# SwitchingPowerSupplyCourse.net
KiCad netlist of a schematic drawn in Altium Designer
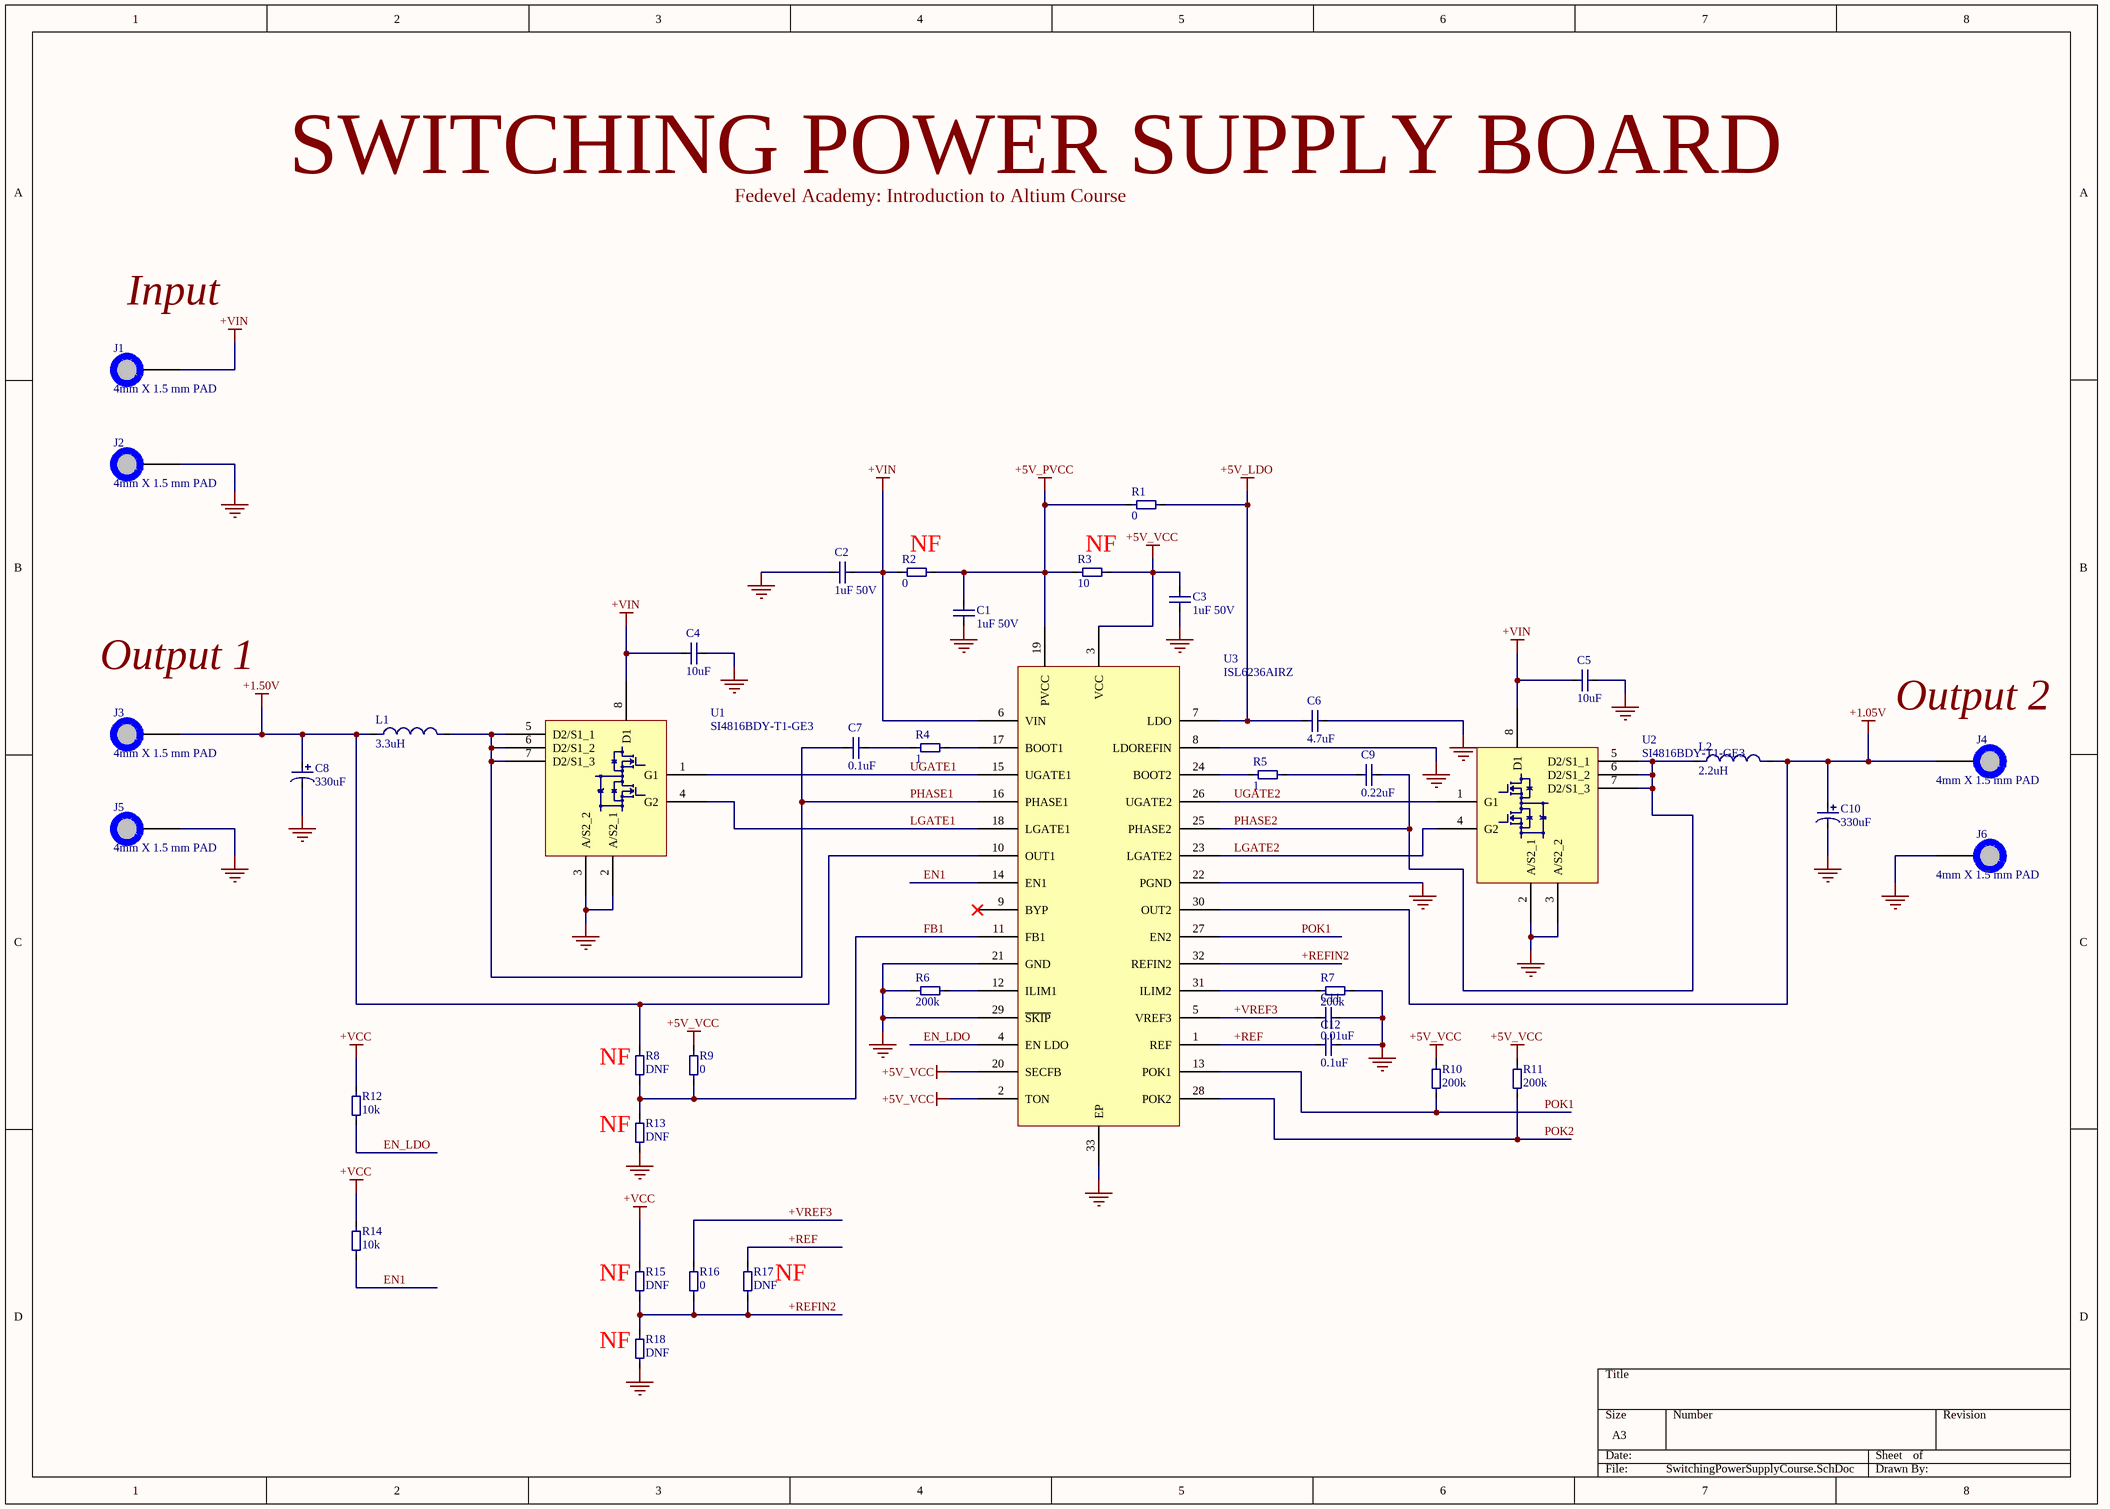
[diagram p0: SwitchingPowerSupplyCourse.SchDoc]

(export (version "E")
  (design (tool "Eeschema 10.0.6"))
  (components
    (comp (ref "C1")
      (value "1uF 50V")
      (footprint "C0805")
      (description "Multilayer Ceramic Capacitors MLCC - SMD/SMT CAP MLCC 0805 50V Y5V 1uF +80/-20%")
      (fields
        (field (name "MANUFACTURER") "Taiyo Yuden")
        (field (name "MANUFACTURER PART NUMBER") "UMK212F105ZG-T")
      )
      (libsource (lib "SwitchingPowerSupplyCourse_Symbols") (part "UMK212F105ZG-T"))
    )
    (comp (ref "C2")
      (value "1uF 50V")
      (footprint "C0805")
      (description "Multilayer Ceramic Capacitors MLCC - SMD/SMT CAP MLCC 0805 50V Y5V 1uF +80/-20%")
      (fields
        (field (name "MANUFACTURER") "Taiyo Yuden")
        (field (name "MANUFACTURER PART NUMBER") "UMK212F105ZG-T")
      )
      (libsource (lib "SwitchingPowerSupplyCourse_Symbols") (part "UMK212F105ZG-T"))
    )
    (comp (ref "C3")
      (value "1uF 50V")
      (footprint "C0805")
      (description "Multilayer Ceramic Capacitors MLCC - SMD/SMT CAP MLCC 0805 50V Y5V 1uF +80/-20%")
      (fields
        (field (name "MANUFACTURER") "Taiyo Yuden")
        (field (name "MANUFACTURER PART NUMBER") "UMK212F105ZG-T")
      )
      (libsource (lib "SwitchingPowerSupplyCourse_Symbols") (part "UMK212F105ZG-T"))
    )
    (comp (ref "C4")
      (value "10uF")
      (footprint "C1210")
      (description "Multilayer Ceramic Capacitors MLCC - SMD/SMT CAP MLCC 1210 50V X5R 10uF 20%")
      (fields
        (field (name "MANUFACTURER") "Taiyo Yuden")
        (field (name "MANUFACTURER PART NUMBER") "UMK325BJ106MM-T")
      )
      (libsource (lib "SwitchingPowerSupplyCourse_Symbols") (part "UMK325BJ106MM-T"))
    )
    (comp (ref "C5")
      (value "10uF")
      (footprint "C1210")
      (description "Multilayer Ceramic Capacitors MLCC - SMD/SMT CAP MLCC 1210 50V X5R 10uF 20%")
      (fields
        (field (name "MANUFACTURER") "Taiyo Yuden")
        (field (name "MANUFACTURER PART NUMBER") "UMK325BJ106MM-T")
      )
      (libsource (lib "SwitchingPowerSupplyCourse_Symbols") (part "UMK325BJ106MM-T"))
    )
    (comp (ref "C6")
      (value "4.7uF")
      (footprint "C1206")
      (description "Multilayer Ceramic Capacitors MLCC - SMD/SMT 1206 4.7uF 10volts X5R 10%")
      (fields (field (name "MANUFACTURER") "AVX") (field (name "MANUFACTURER PART NUMBER") "1206ZD475KAT2A"))
      (libsource (lib "SwitchingPowerSupplyCourse_Symbols") (part "1206ZD475KAT2A"))
    )
    (comp (ref "C7")
      (value "0.1uF")
      (footprint "C0805")
      (description "Multilayer Ceramic Capacitors MLCC - SMD/SMT 50volts 0.1uF 10%")
      (fields
        (field (name "MANUFACTURER") "Syfer")
        (field (name "MANUFACTURER PART NUMBER") "0805J0500104KJT")
      )
      (libsource (lib "SwitchingPowerSupplyCourse_Symbols") (part "0805J0500104KJT"))
    )
    (comp (ref "C8")
      (value "330uF")
      (footprint "7343-31")
      (description "Tantalum Capacitors - Solid SMD 10volts 330uF 10% ESR=150mOhms")
      (fields
        (field (name "MANUFACTURER") "Kemet")
        (field (name "MANUFACTURER PART NUMBER") "T495D337K010ATE150")
      )
      (libsource (lib "SwitchingPowerSupplyCourse_Symbols") (part "T495D337K010ATE150"))
    )
    (comp (ref "C9")
      (value "0.22uF")
      (footprint "C0805")
      (description "Multilayer Ceramic Capacitors MLCC - SMD/SMT CAP MLCC 0805 50V X7R 0.22uF 10%")
      (fields
        (field (name "MANUFACTURER") "Taiyo Yuden")
        (field (name "MANUFACTURER PART NUMBER") "UMK212B7224KG-T")
      )
      (libsource (lib "SwitchingPowerSupplyCourse_Symbols") (part "UMK212B7224KG-T"))
    )
    (comp (ref "C10")
      (value "330uF")
      (footprint "7343-31")
      (description "Tantalum Capacitors - Solid SMD 10volts 330uF 10% ESR=150mOhms")
      (fields
        (field (name "MANUFACTURER") "Kemet")
        (field (name "MANUFACTURER PART NUMBER") "T495D337K010ATE150")
      )
      (libsource (lib "SwitchingPowerSupplyCourse_Symbols") (part "T495D337K010ATE150"))
    )
    (comp (ref "C11")
      (value "0.01uF")
      (footprint "C0805")
      (description "Multilayer Ceramic Capacitors MLCC - SMD/SMT 0805 0.01uF 50volts X7R 5%")
      (fields
        (field (name "MANUFACTURER") "Vishay / Vitramon")
        (field (name "MANUFACTURER PART NUMBER") "VJ0805Y103JXAPW1BC")
      )
      (libsource (lib "SwitchingPowerSupplyCourse_Symbols") (part "VJ0805Y103JXAPW1BC"))
    )
    (comp (ref "C12")
      (value "0.1uF")
      (footprint "C0805")
      (description "Multilayer Ceramic Capacitors MLCC - SMD/SMT 50volts 0.1uF 10%")
      (fields
        (field (name "MANUFACTURER") "Syfer")
        (field (name "MANUFACTURER PART NUMBER") "0805J0500104KJT")
      )
      (libsource (lib "SwitchingPowerSupplyCourse_Symbols") (part "0805J0500104KJT"))
    )
    (comp (ref "J1")
      (value "4mm X 1.5 mm PAD")
      (footprint "PAD_WITH_HOLE_4mmX1.5mm")
      (description "Elliptical pad 4mm x 1.5 mm")
      (libsource (lib "SwitchingPowerSupplyCourse_Symbols") (part "4mmX1.5mm_PAD"))
    )
    (comp (ref "J2")
      (value "4mm X 1.5 mm PAD")
      (footprint "PAD_WITH_HOLE_4mmX1.5mm")
      (description "Elliptical pad 4mm x 1.5 mm")
      (libsource (lib "SwitchingPowerSupplyCourse_Symbols") (part "4mmX1.5mm_PAD"))
    )
    (comp (ref "J3")
      (value "4mm X 1.5 mm PAD")
      (footprint "PAD_WITH_HOLE_4mmX1.5mm")
      (description "Elliptical pad 4mm x 1.5 mm")
      (libsource (lib "SwitchingPowerSupplyCourse_Symbols") (part "4mmX1.5mm_PAD"))
    )
    (comp (ref "J4")
      (value "4mm X 1.5 mm PAD")
      (footprint "PAD_WITH_HOLE_4mmX1.5mm")
      (description "Elliptical pad 4mm x 1.5 mm")
      (libsource (lib "SwitchingPowerSupplyCourse_Symbols") (part "4mmX1.5mm_PAD"))
    )
    (comp (ref "J5")
      (value "4mm X 1.5 mm PAD")
      (footprint "PAD_WITH_HOLE_4mmX1.5mm")
      (description "Elliptical pad 4mm x 1.5 mm")
      (libsource (lib "SwitchingPowerSupplyCourse_Symbols") (part "4mmX1.5mm_PAD"))
    )
    (comp (ref "J6")
      (value "4mm X 1.5 mm PAD")
      (footprint "PAD_WITH_HOLE_4mmX1.5mm")
      (description "Elliptical pad 4mm x 1.5 mm")
      (libsource (lib "SwitchingPowerSupplyCourse_Symbols") (part "4mmX1.5mm_PAD"))
    )
    (comp (ref "L1")
      (value "3.3uH")
      (footprint "SRP1265A")
      (description "Fixed Inductors 3.3uH 20% SMD 1265")
      (fields
        (field (name "MANUFACTURER") "Bourns")
        (field (name "MANUFACTURER PART NUMBER") "SRP1265A-3R3M")
      )
      (libsource (lib "SwitchingPowerSupplyCourse_Symbols") (part "SRP1265A-3R3M"))
    )
    (comp (ref "L2")
      (value "2.2uH")
      (footprint "SRP1265A")
      (description "Fixed Inductors 2.2uH 20% SMD 1265")
      (fields
        (field (name "MANUFACTURER") "Bourns")
        (field (name "MANUFACTURER PART NUMBER") "SRP1265A-2R2M")
      )
      (libsource (lib "SwitchingPowerSupplyCourse_Symbols") (part "SRP1265A-2R2M"))
    )
    (comp (ref "R1")
      (value "0")
      (footprint "R0805")
      (description "Thick Film Resistors - SMD ZEROohms JUMPER")
      (fields
        (field (name "MANUFACTURER") "KOA Speer")
        (field (name "MANUFACTURER PART NUMBER") "RK73Z2ATTD")
      )
      (libsource (lib "SwitchingPowerSupplyCourse_Symbols") (part "RK73Z2ATTD"))
    )
    (comp (ref "R2")
      (value "0")
      (footprint "R0805")
      (description "Thick Film Resistors - SMD ZEROohms JUMPER")
      (fields
        (field (name "MANUFACTURER") "KOA Speer")
        (field (name "MANUFACTURER PART NUMBER") "RK73Z2ATTD")
      )
      (libsource (lib "SwitchingPowerSupplyCourse_Symbols") (part "RK73Z2ATTD"))
    )
    (comp (ref "R3")
      (value "10")
      (footprint "R0805")
      (description "Thick Film Resistors - SMD 1/8watt 10ohms 1% 100ppm")
      (fields
        (field (name "MANUFACTURER") "Vishay / Dale")
        (field (name "MANUFACTURER PART NUMBER") "CRCW080510R0FKEA")
      )
      (libsource (lib "SwitchingPowerSupplyCourse_Symbols") (part "CRCW080510R0FKEA"))
    )
    (comp (ref "R4")
      (value "1")
      (footprint "R0805")
      (description "Thick Film Resistors - SMD 1/8watt 1ohms 100ppm")
      (fields
        (field (name "MANUFACTURER") "Vishay / Dale")
        (field (name "MANUFACTURER PART NUMBER") "CRCW08051R00FKEA")
      )
      (libsource (lib "SwitchingPowerSupplyCourse_Symbols") (part "CRCW08051R00FKEA"))
    )
    (comp (ref "R5")
      (value "1")
      (footprint "R0805")
      (description "Thick Film Resistors - SMD 1/8watt 1ohms 100ppm")
      (fields
        (field (name "MANUFACTURER") "Vishay / Dale")
        (field (name "MANUFACTURER PART NUMBER") "CRCW08051R00FKEA")
      )
      (libsource (lib "SwitchingPowerSupplyCourse_Symbols") (part "CRCW08051R00FKEA"))
    )
    (comp (ref "R6")
      (value "200k")
      (footprint "R0805")
      (description "Thick Film Resistors - SMD 1/8watts 200Kohms 1%")
      (fields
        (field (name "MANUFACTURER") "KOA Speer")
        (field (name "MANUFACTURER PART NUMBER") "RK73H2ATTD2003F")
      )
      (libsource (lib "SwitchingPowerSupplyCourse_Symbols") (part "RK73H2ATTD2003F"))
    )
    (comp (ref "R7")
      (value "200k")
      (footprint "R0805")
      (description "Thick Film Resistors - SMD 1/8watts 200Kohms 1%")
      (fields
        (field (name "MANUFACTURER") "KOA Speer")
        (field (name "MANUFACTURER PART NUMBER") "RK73H2ATTD2003F")
      )
      (libsource (lib "SwitchingPowerSupplyCourse_Symbols") (part "RK73H2ATTD2003F"))
    )
    (comp (ref "R8")
      (value "DNF")
      (footprint "R0805")
      (description "Generic Do Not Fit Capacitor")
      (libsource (lib "SwitchingPowerSupplyCourse_Symbols") (part "RES"))
    )
    (comp (ref "R9")
      (value "0")
      (footprint "R0805")
      (description "Thick Film Resistors - SMD ZEROohms JUMPER")
      (fields
        (field (name "MANUFACTURER") "KOA Speer")
        (field (name "MANUFACTURER PART NUMBER") "RK73Z2ATTD")
      )
      (libsource (lib "SwitchingPowerSupplyCourse_Symbols") (part "RK73Z2ATTD"))
    )
    (comp (ref "R10")
      (value "200k")
      (footprint "R0805")
      (description "Thick Film Resistors - SMD 1/8watts 200Kohms 1%")
      (fields
        (field (name "MANUFACTURER") "KOA Speer")
        (field (name "MANUFACTURER PART NUMBER") "RK73H2ATTD2003F")
      )
      (libsource (lib "SwitchingPowerSupplyCourse_Symbols") (part "RK73H2ATTD2003F"))
    )
    (comp (ref "R11")
      (value "200k")
      (footprint "R0805")
      (description "Thick Film Resistors - SMD 1/8watts 200Kohms 1%")
      (fields
        (field (name "MANUFACTURER") "KOA Speer")
        (field (name "MANUFACTURER PART NUMBER") "RK73H2ATTD2003F")
      )
      (libsource (lib "SwitchingPowerSupplyCourse_Symbols") (part "RK73H2ATTD2003F"))
    )
    (comp (ref "R12")
      (value "10k")
      (footprint "R0805")
      (description "Thick Film Resistors - SMD 0.25W 10Kohm 1% 200ppm")
      (fields
        (field (name "MANUFACTURER") "KOA Speer")
        (field (name "MANUFACTURER PART NUMBER") "SG73P2ATTD1002F")
      )
      (libsource (lib "SwitchingPowerSupplyCourse_Symbols") (part "SG73P2ATTD1002F"))
    )
    (comp (ref "R13")
      (value "DNF")
      (footprint "R0805")
      (description "Generic Do Not Fit Capacitor")
      (libsource (lib "SwitchingPowerSupplyCourse_Symbols") (part "RES"))
    )
    (comp (ref "R14")
      (value "10k")
      (footprint "R0805")
      (description "Thick Film Resistors - SMD 0.25W 10Kohm 1% 200ppm")
      (fields
        (field (name "MANUFACTURER") "KOA Speer")
        (field (name "MANUFACTURER PART NUMBER") "SG73P2ATTD1002F")
      )
      (libsource (lib "SwitchingPowerSupplyCourse_Symbols") (part "SG73P2ATTD1002F"))
    )
    (comp (ref "R15")
      (value "DNF")
      (footprint "R0805")
      (description "Generic Do Not Fit Capacitor")
      (libsource (lib "SwitchingPowerSupplyCourse_Symbols") (part "RES"))
    )
    (comp (ref "R16")
      (value "0")
      (footprint "R0805")
      (description "Thick Film Resistors - SMD ZEROohms JUMPER")
      (fields
        (field (name "MANUFACTURER") "KOA Speer")
        (field (name "MANUFACTURER PART NUMBER") "RK73Z2ATTD")
      )
      (libsource (lib "SwitchingPowerSupplyCourse_Symbols") (part "RK73Z2ATTD"))
    )
    (comp (ref "R17")
      (value "DNF")
      (footprint "R0805")
      (description "Generic Do Not Fit Capacitor")
      (libsource (lib "SwitchingPowerSupplyCourse_Symbols") (part "RES"))
    )
    (comp (ref "R18")
      (value "DNF")
      (footprint "R0805")
      (description "Generic Do Not Fit Capacitor")
      (libsource (lib "SwitchingPowerSupplyCourse_Symbols") (part "RES"))
    )
    (comp (ref "U1")
      (value "SI4816BDY-T1-GE3")
      (footprint "SO-8")
      (description "MOSFET Dua lN-Ch w/Schottky 30V 18.5/11.5mohm")
      (fields (field (name "MANUFACTURER") "Vishay / Siliconix"))
      (libsource (lib "SwitchingPowerSupplyCourse_Symbols") (part "SI4816BDY-T1-GE3"))
    )
    (comp (ref "U2")
      (value "SI4816BDY-T1-GE3")
      (footprint "SO-8")
      (description "MOSFET Dua lN-Ch w/Schottky 30V 18.5/11.5mohm")
      (fields (field (name "MANUFACTURER") "Vishay / Siliconix"))
      (libsource (lib "SwitchingPowerSupplyCourse_Symbols") (part "SI4816BDY-T1-GE3"))
    )
    (comp (ref "U3")
      (value "ISL6236AIRZ")
      (footprint "L32.5x5B")
      (description "Switching Controllers ISL6236 QD QUTPUT CNTRLR IMVP-6 32LD")
      (fields (field (name "MANUFACTURER") "Intersil"))
      (libsource (lib "SwitchingPowerSupplyCourse_Symbols") (part "ISL6236AIRZ"))
    )
  )
  (nets
    (net (code "1") (name "+1.05V") (class "Default")
      (node (ref "C10") (pin "1") (pinfunction "1_1") (pintype "passive"))
      (node (ref "J4") (pin "1") (pinfunction "1_1") (pintype "passive"))
      (node (ref "L2") (pin "2") (pinfunction "2_2") (pintype "passive"))
      (node (ref "U3") (pin "30") (pinfunction "OUT2_30") (pintype "passive"))
    )
    (net (code "2") (name "+1.50V") (class "Default")
      (node (ref "C8") (pin "1") (pinfunction "1_1") (pintype "passive"))
      (node (ref "J3") (pin "1") (pinfunction "1_1") (pintype "passive"))
      (node (ref "L1") (pin "1") (pinfunction "1_1") (pintype "passive"))
      (node (ref "R8") (pin "2") (pinfunction "2_2") (pintype "passive"))
      (node (ref "U3") (pin "10") (pinfunction "OUT1_10") (pintype "passive"))
    )
    (net (code "3") (name "+5V_LDO") (class "Default")
      (node (ref "C6") (pin "2") (pinfunction "2_2") (pintype "passive"))
      (node (ref "R1") (pin "2") (pinfunction "2_2") (pintype "passive"))
      (node (ref "U3") (pin "7") (pinfunction "LDO_7") (pintype "passive"))
    )
    (net (code "4") (name "+5V_PVCC") (class "Default")
      (node (ref "C1") (pin "2") (pinfunction "2_2") (pintype "passive"))
      (node (ref "R1") (pin "1") (pinfunction "1_1") (pintype "passive"))
      (node (ref "R2") (pin "2") (pinfunction "2_2") (pintype "passive"))
      (node (ref "R3") (pin "1") (pinfunction "1_1") (pintype "passive"))
      (node (ref "U3") (pin "19") (pinfunction "PVCC_19") (pintype "passive"))
    )
    (net (code "5") (name "+5V_VCC") (class "Default")
      (node (ref "C3") (pin "1") (pinfunction "1_1") (pintype "passive"))
      (node (ref "R10") (pin "1") (pinfunction "1_1") (pintype "passive"))
      (node (ref "R11") (pin "1") (pinfunction "1_1") (pintype "passive"))
      (node (ref "R3") (pin "2") (pinfunction "2_2") (pintype "passive"))
      (node (ref "R9") (pin "2") (pinfunction "2_2") (pintype "passive"))
      (node (ref "U3") (pin "2") (pinfunction "TON_2") (pintype "passive"))
      (node (ref "U3") (pin "20") (pinfunction "SECFB_20") (pintype "passive"))
      (node (ref "U3") (pin "3") (pinfunction "VCC_3") (pintype "passive"))
    )
    (net (code "6") (name "+VCC") (class "Default")
      (node (ref "R12") (pin "2") (pinfunction "2_2") (pintype "passive"))
      (node (ref "R14") (pin "2") (pinfunction "2_2") (pintype "passive"))
      (node (ref "R15") (pin "2") (pinfunction "2_2") (pintype "passive"))
    )
    (net (code "7") (name "+VIN") (class "Default")
      (node (ref "C2") (pin "2") (pinfunction "2_2") (pintype "passive"))
      (node (ref "C4") (pin "1") (pinfunction "1_1") (pintype "passive"))
      (node (ref "C5") (pin "1") (pinfunction "1_1") (pintype "passive"))
      (node (ref "J1") (pin "1") (pinfunction "1_1") (pintype "passive"))
      (node (ref "R2") (pin "1") (pinfunction "1_1") (pintype "passive"))
      (node (ref "U1") (pin "8") (pinfunction "D1_8") (pintype "passive"))
      (node (ref "U2") (pin "8") (pinfunction "D1_8") (pintype "passive"))
      (node (ref "U3") (pin "6") (pinfunction "VIN_6") (pintype "passive"))
    )
    (net (code "8") (name "/+REF") (class "Default")
      (node (ref "C12") (pin "1") (pinfunction "1_1") (pintype "passive"))
      (node (ref "R17") (pin "2") (pinfunction "2_2") (pintype "passive"))
      (node (ref "U3") (pin "1") (pinfunction "REF_1") (pintype "passive"))
    )
    (net (code "9") (name "/+REFIN2") (class "Default")
      (node (ref "R15") (pin "1") (pinfunction "1_1") (pintype "passive"))
      (node (ref "R16") (pin "1") (pinfunction "1_1") (pintype "passive"))
      (node (ref "R17") (pin "1") (pinfunction "1_1") (pintype "passive"))
      (node (ref "R18") (pin "2") (pinfunction "2_2") (pintype "passive"))
      (node (ref "U3") (pin "32") (pinfunction "REFIN2_32") (pintype "passive"))
    )
    (net (code "10") (name "/+VREF3") (class "Default")
      (node (ref "C11") (pin "1") (pinfunction "1_1") (pintype "passive"))
      (node (ref "R16") (pin "2") (pinfunction "2_2") (pintype "passive"))
      (node (ref "U3") (pin "5") (pinfunction "VREF3_5") (pintype "passive"))
    )
    (net (code "11") (name "/EN1") (class "Default")
      (node (ref "R14") (pin "1") (pinfunction "1_1") (pintype "passive"))
      (node (ref "U3") (pin "14") (pinfunction "EN1_14") (pintype "passive"))
    )
    (net (code "12") (name "/EN_LDO") (class "Default")
      (node (ref "R12") (pin "1") (pinfunction "1_1") (pintype "passive"))
      (node (ref "U3") (pin "4") (pinfunction "EN_LDO_4") (pintype "passive"))
    )
    (net (code "13") (name "/FB1") (class "Default")
      (node (ref "R13") (pin "2") (pinfunction "2_2") (pintype "passive"))
      (node (ref "R8") (pin "1") (pinfunction "1_1") (pintype "passive"))
      (node (ref "R9") (pin "1") (pinfunction "1_1") (pintype "passive"))
      (node (ref "U3") (pin "11") (pinfunction "FB1_11") (pintype "passive"))
    )
    (net (code "14") (name "/LGATE1") (class "Default")
      (node (ref "U1") (pin "4") (pinfunction "G2_4") (pintype "passive"))
      (node (ref "U3") (pin "18") (pinfunction "LGATE1_18") (pintype "passive"))
    )
    (net (code "15") (name "/LGATE2") (class "Default")
      (node (ref "U2") (pin "4") (pinfunction "G2_4") (pintype "passive"))
      (node (ref "U3") (pin "23") (pinfunction "LGATE2_23") (pintype "passive"))
    )
    (net (code "16") (name "/PHASE1") (class "Default")
      (node (ref "C7") (pin "1") (pinfunction "1_1") (pintype "passive"))
      (node (ref "L1") (pin "2") (pinfunction "2_2") (pintype "passive"))
      (node (ref "U1") (pin "5") (pinfunction "D2/S1_1_5") (pintype "passive"))
      (node (ref "U1") (pin "6") (pinfunction "D2/S1_2_6") (pintype "passive"))
      (node (ref "U1") (pin "7") (pinfunction "D2/S1_3_7") (pintype "passive"))
      (node (ref "U3") (pin "16") (pinfunction "PHASE1_16") (pintype "passive"))
    )
    (net (code "17") (name "/PHASE2") (class "Default")
      (node (ref "C9") (pin "2") (pinfunction "2_2") (pintype "passive"))
      (node (ref "L2") (pin "1") (pinfunction "1_1") (pintype "passive"))
      (node (ref "U2") (pin "5") (pinfunction "D2/S1_1_5") (pintype "passive"))
      (node (ref "U2") (pin "6") (pinfunction "D2/S1_2_6") (pintype "passive"))
      (node (ref "U2") (pin "7") (pinfunction "D2/S1_3_7") (pintype "passive"))
      (node (ref "U3") (pin "25") (pinfunction "PHASE2_25") (pintype "passive"))
    )
    (net (code "18") (name "/POK1") (class "Default")
      (node (ref "R10") (pin "2") (pinfunction "2_2") (pintype "passive"))
      (node (ref "U3") (pin "13") (pinfunction "POK1_13") (pintype "passive"))
      (node (ref "U3") (pin "27") (pinfunction "EN2_27") (pintype "passive"))
    )
    (net (code "19") (name "/POK2") (class "Default")
      (node (ref "R11") (pin "2") (pinfunction "2_2") (pintype "passive"))
      (node (ref "U3") (pin "28") (pinfunction "POK2_28") (pintype "passive"))
    )
    (net (code "20") (name "/UGATE1") (class "Default")
      (node (ref "U1") (pin "1") (pinfunction "G1_1") (pintype "passive"))
      (node (ref "U3") (pin "15") (pinfunction "UGATE1_15") (pintype "passive"))
    )
    (net (code "21") (name "/UGATE2") (class "Default")
      (node (ref "U2") (pin "1") (pinfunction "G1_1") (pintype "passive"))
      (node (ref "U3") (pin "26") (pinfunction "UGATE2_26") (pintype "passive"))
    )
    (net (code "22") (name "GND") (class "Default")
      (node (ref "C1") (pin "1") (pinfunction "1_1") (pintype "passive"))
      (node (ref "C10") (pin "2") (pinfunction "2_2") (pintype "passive"))
      (node (ref "C11") (pin "2") (pinfunction "2_2") (pintype "passive"))
      (node (ref "C12") (pin "2") (pinfunction "2_2") (pintype "passive"))
      (node (ref "C2") (pin "1") (pinfunction "1_1") (pintype "passive"))
      (node (ref "C3") (pin "2") (pinfunction "2_2") (pintype "passive"))
      (node (ref "C4") (pin "2") (pinfunction "2_2") (pintype "passive"))
      (node (ref "C5") (pin "2") (pinfunction "2_2") (pintype "passive"))
      (node (ref "C6") (pin "1") (pinfunction "1_1") (pintype "passive"))
      (node (ref "C8") (pin "2") (pinfunction "2_2") (pintype "passive"))
      (node (ref "J2") (pin "1") (pinfunction "1_1") (pintype "passive"))
      (node (ref "J5") (pin "1") (pinfunction "1_1") (pintype "passive"))
      (node (ref "J6") (pin "1") (pinfunction "1_1") (pintype "passive"))
      (node (ref "R13") (pin "1") (pinfunction "1_1") (pintype "passive"))
      (node (ref "R18") (pin "1") (pinfunction "1_1") (pintype "passive"))
      (node (ref "R6") (pin "1") (pinfunction "1_1") (pintype "passive"))
      (node (ref "R7") (pin "2") (pinfunction "2_2") (pintype "passive"))
      (node (ref "U1") (pin "2") (pinfunction "A/S2_1_2") (pintype "passive"))
      (node (ref "U1") (pin "3") (pinfunction "A/S2_2_3") (pintype "passive"))
      (node (ref "U2") (pin "2") (pinfunction "A/S2_1_2") (pintype "passive"))
      (node (ref "U2") (pin "3") (pinfunction "A/S2_2_3") (pintype "passive"))
      (node (ref "U3") (pin "21") (pinfunction "GND_21") (pintype "passive"))
      (node (ref "U3") (pin "22") (pinfunction "PGND_22") (pintype "passive"))
      (node (ref "U3") (pin "29") (pinfunction "~{SKIP}_29") (pintype "passive"))
      (node (ref "U3") (pin "33") (pinfunction "EP_33") (pintype "passive"))
      (node (ref "U3") (pin "8") (pinfunction "LDOREFIN_8") (pintype "passive"))
    )
    (net (code "23") (name "Net-(C7-Pad2)") (class "Default")
      (node (ref "C7") (pin "2") (pinfunction "2_2") (pintype "passive"))
      (node (ref "R4") (pin "1") (pinfunction "1_1") (pintype "passive"))
    )
    (net (code "24") (name "Net-(C9-Pad1)") (class "Default")
      (node (ref "C9") (pin "1") (pinfunction "1_1") (pintype "passive"))
      (node (ref "R5") (pin "2") (pinfunction "2_2") (pintype "passive"))
    )
    (net (code "25") (name "Net-(U3-BOOT1)") (class "Default")
      (node (ref "R4") (pin "2") (pinfunction "2_2") (pintype "passive"))
      (node (ref "U3") (pin "17") (pinfunction "BOOT1_17") (pintype "passive"))
    )
    (net (code "26") (name "Net-(U3-BOOT2)") (class "Default")
      (node (ref "R5") (pin "1") (pinfunction "1_1") (pintype "passive"))
      (node (ref "U3") (pin "24") (pinfunction "BOOT2_24") (pintype "passive"))
    )
    (net (code "27") (name "Net-(U3-ILIM1)") (class "Default")
      (node (ref "R6") (pin "2") (pinfunction "2_2") (pintype "passive"))
      (node (ref "U3") (pin "12") (pinfunction "ILIM1_12") (pintype "passive"))
    )
    (net (code "28") (name "Net-(U3-ILIM2)") (class "Default")
      (node (ref "R7") (pin "1") (pinfunction "1_1") (pintype "passive"))
      (node (ref "U3") (pin "31") (pinfunction "ILIM2_31") (pintype "passive"))
    )
    (net (code "29") (name "unconnected-(U3-BYP-Pad9)") (class "Default")
      (node (ref "U3") (pin "9") (pinfunction "BYP_9") (pintype "passive+no_connect"))
    )
  )
)
